# power_supply_7805.net
KiCad netlist of a schematic drawn in EasyEDA
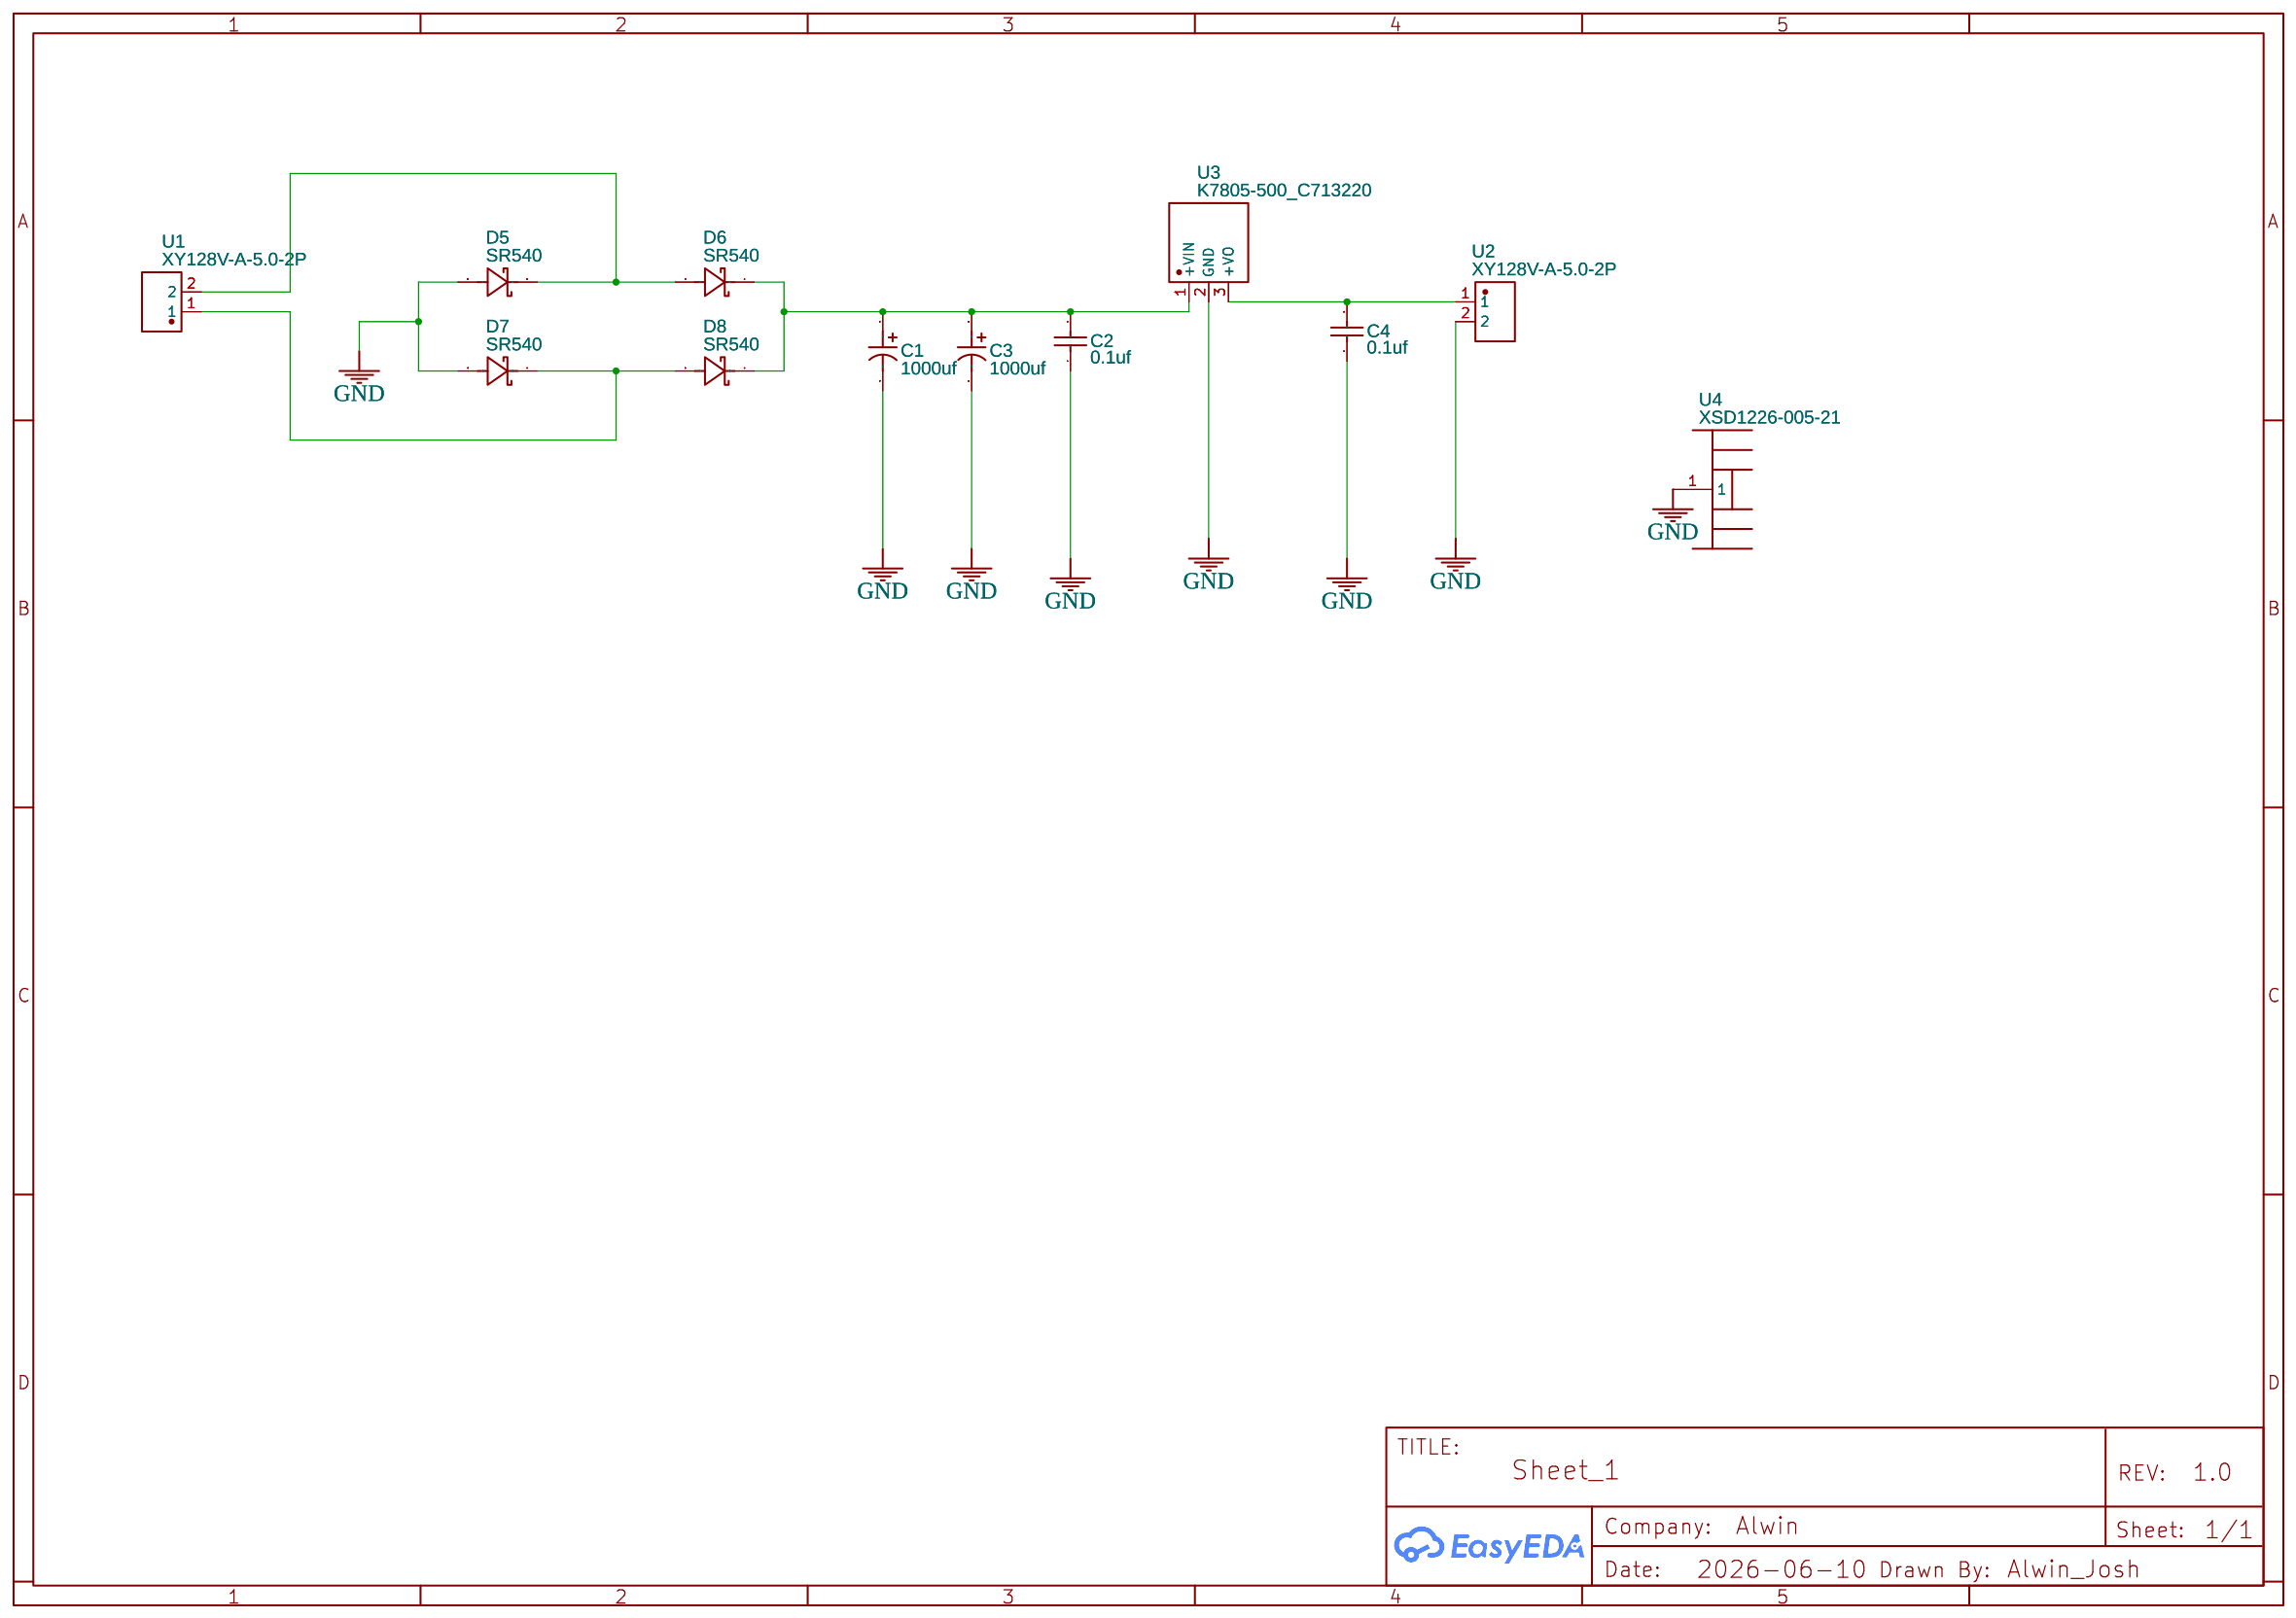
[diagram p0: schematic sheet]

(export (version "E")
  (design (tool "Eeschema 10.0.6"))
  (components
    (comp (ref "C1")
      (value "1000uf")
      (fields
        (field (name "Manufacturer Part") "RVT2A4R7M0607ZY")
        (field (name "Manufacturer") "ChengTao(诚韬)")
      )
      (libsource (lib "") (part "RVT2A4R7M0607ZY"))
    )
    (comp (ref "C2")
      (value "0.1uf")
      (fields (field (name "Manufacturer Part") "CT4-0805Y104M500") (field (name "Manufacturer") "LCSC"))
      (libsource (lib "") (part "0.1uf"))
    )
    (comp (ref "C3")
      (value "1000uf")
      (fields
        (field (name "Manufacturer Part") "RVT2A4R7M0607ZY")
        (field (name "Manufacturer") "ChengTao(诚韬)")
      )
      (libsource (lib "") (part "RVT2A4R7M0607ZY"))
    )
    (comp (ref "C4")
      (value "0.1uf")
      (fields (field (name "Manufacturer Part") "CT4-0805Y104M500") (field (name "Manufacturer") "LCSC"))
      (libsource (lib "") (part "0.1uf"))
    )
    (comp (ref "D5")
      (value "SR540")
      (fields (field (name "Manufacturer") "XUMAO(旭茂微)"))
      (libsource (lib "") (part "SR540_C22448098"))
    )
    (comp (ref "D6")
      (value "SR540")
      (fields (field (name "Manufacturer") "XUMAO(旭茂微)"))
      (libsource (lib "") (part "SR540_C22448098"))
    )
    (comp (ref "D7")
      (value "SR540")
      (fields (field (name "Manufacturer") "XUMAO(旭茂微)"))
      (libsource (lib "") (part "SR540_C22448098"))
    )
    (comp (ref "D8")
      (value "SR540")
      (fields (field (name "Manufacturer") "XUMAO(旭茂微)"))
      (libsource (lib "") (part "SR540_C22448098"))
    )
    (comp (ref "U1")
      (value "XY128V-A-5.0-2P")
      (fields (field (name "Manufacturer") "XINLAIYA(新莱亚)"))
      (libsource (lib "") (part "XY128V-A-5.0-2P"))
    )
    (comp (ref "U2")
      (value "XY128V-A-5.0-2P")
      (fields (field (name "Manufacturer") "XINLAIYA(新莱亚)"))
      (libsource (lib "") (part "XY128V-A-5.0-2P_1"))
    )
    (comp (ref "U3")
      (value "K7805-500_C713220")
      (fields (field (name "Manufacturer Part") "K7805-500") (field (name "Manufacturer") "rlt"))
      (libsource (lib "") (part "K7805-500_C713220"))
    )
    (comp (ref "U4")
      (value "XSD1226-005-21")
      (fields (field (name "Manufacturer") "XSD(鑫顺达)"))
      (libsource (lib "") (part "XSD1226-005-21"))
    )
  )
  (nets
    (net (code "1") (name "GND") (class "Default")
      (node (ref "C1") (pin "2") (pinfunction "2_2") (pintype "input"))
      (node (ref "C2") (pin "1") (pinfunction "1_1") (pintype "input"))
      (node (ref "C3") (pin "2") (pinfunction "2_2") (pintype "input"))
      (node (ref "C4") (pin "1") (pinfunction "1_1") (pintype "input"))
      (node (ref "D5") (pin "2") (pinfunction "A_2") (pintype "unspecified"))
      (node (ref "D7") (pin "2") (pinfunction "A_2") (pintype "unspecified"))
      (node (ref "U2") (pin "2") (pinfunction "2_2") (pintype "unspecified"))
      (node (ref "U3") (pin "2") (pinfunction "GND_2") (pintype "unspecified"))
      (node (ref "U4") (pin "1") (pinfunction "1_1") (pintype "unspecified"))
    )
    (net (code "2") (name "Net-(D5-C)") (class "Default")
      (node (ref "D5") (pin "1") (pinfunction "C_1") (pintype "unspecified"))
      (node (ref "D6") (pin "2") (pinfunction "A_2") (pintype "unspecified"))
      (node (ref "U1") (pin "2") (pinfunction "2_2") (pintype "unspecified"))
    )
    (net (code "3") (name "Net-(D6-C)") (class "Default")
      (node (ref "C1") (pin "1") (pinfunction "1_1") (pintype "input"))
      (node (ref "C2") (pin "2") (pinfunction "2_2") (pintype "input"))
      (node (ref "C3") (pin "1") (pinfunction "1_1") (pintype "input"))
      (node (ref "D6") (pin "1") (pinfunction "C_1") (pintype "unspecified"))
      (node (ref "D8") (pin "1") (pinfunction "C_1") (pintype "unspecified"))
      (node (ref "U3") (pin "1") (pinfunction "+VIN_1") (pintype "unspecified"))
    )
    (net (code "4") (name "Net-(D7-C)") (class "Default")
      (node (ref "D7") (pin "1") (pinfunction "C_1") (pintype "unspecified"))
      (node (ref "D8") (pin "2") (pinfunction "A_2") (pintype "unspecified"))
      (node (ref "U1") (pin "1") (pinfunction "1_1") (pintype "unspecified"))
    )
    (net (code "5") (name "Net-(U3-+VO)") (class "Default")
      (node (ref "C4") (pin "2") (pinfunction "2_2") (pintype "input"))
      (node (ref "U2") (pin "1") (pinfunction "1_1") (pintype "unspecified"))
      (node (ref "U3") (pin "3") (pinfunction "+VO_3") (pintype "unspecified"))
    )
  )
)
